# dac_wifi.net
KiCad netlist of a schematic drawn in EAGLE
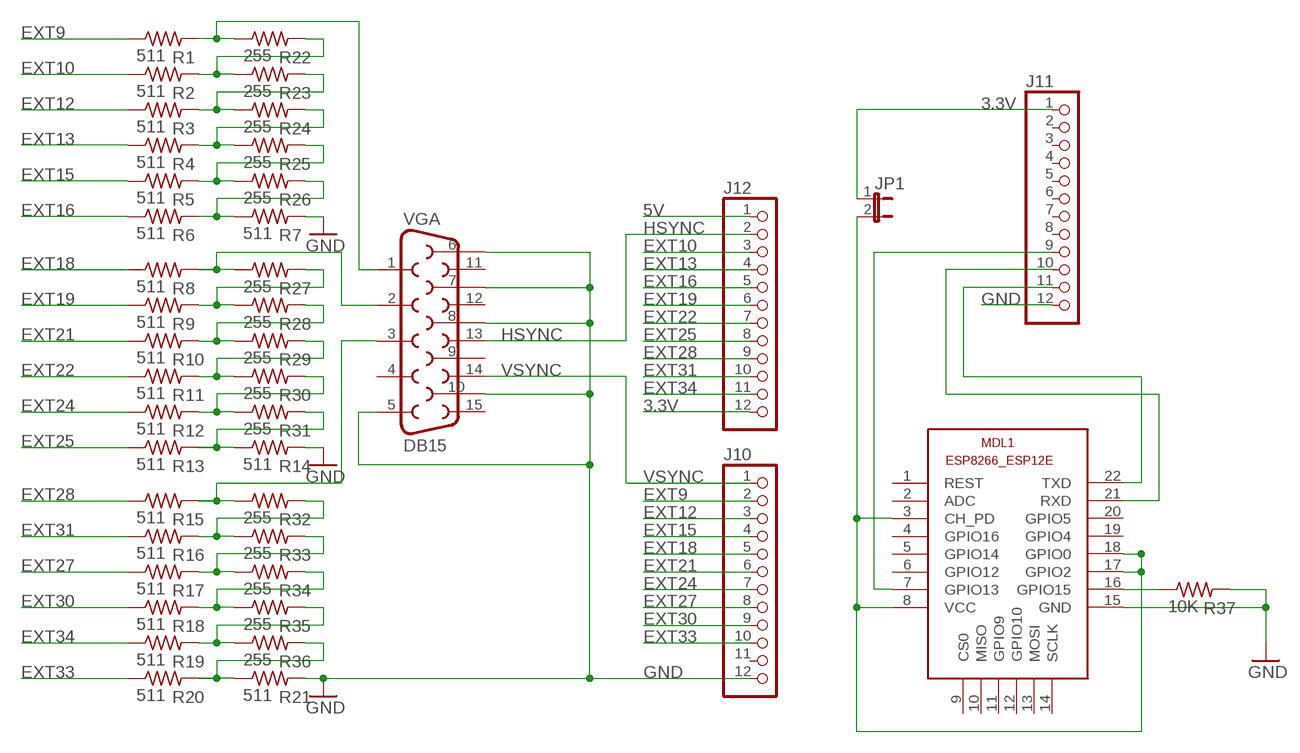
[diagram p0: schematic, sheet 1]

(export (version "E")
  (design (tool "Eeschema 10.0.6"))
  (components
    (comp (ref "J10")
      (value "PINHD-1X12")
      (footprint "eagle-import:1X12")
      (libsource (lib "eagle-import") (part "PINHD-1X12"))
    )
    (comp (ref "J11")
      (value "PINHD-1X12")
      (footprint "eagle-import:1X12")
      (libsource (lib "eagle-import") (part "PINHD-1X12"))
    )
    (comp (ref "J12")
      (value "PINHD-1X12")
      (footprint "eagle-import:1X12")
      (libsource (lib "eagle-import") (part "PINHD-1X12"))
    )
    (comp (ref "JP1")
      (value "JP1E")
      (footprint "eagle-import:JP1")
      (libsource (lib "eagle-import") (part "JP1E"))
    )
    (comp (ref "MDL1")
      (value "ESP8266-12EESP8266-ESP12E")
      (footprint "eagle-import:ESP8266-ESP12E")
      (libsource (lib "eagle-import") (part "ESP8266-12EESP8266-ESP12E"))
    )
    (comp (ref "R1")
      (value "511")
      (footprint "eagle-import:R0805")
      (libsource (lib "eagle-import") (part "R-US_R0805"))
    )
    (comp (ref "R2")
      (value "511")
      (footprint "eagle-import:R0805")
      (libsource (lib "eagle-import") (part "R-US_R0805"))
    )
    (comp (ref "R3")
      (value "511")
      (footprint "eagle-import:R0805")
      (libsource (lib "eagle-import") (part "R-US_R0805"))
    )
    (comp (ref "R4")
      (value "511")
      (footprint "eagle-import:R0805")
      (libsource (lib "eagle-import") (part "R-US_R0805"))
    )
    (comp (ref "R5")
      (value "511")
      (footprint "eagle-import:R0805")
      (libsource (lib "eagle-import") (part "R-US_R0805"))
    )
    (comp (ref "R6")
      (value "511")
      (footprint "eagle-import:R0805")
      (libsource (lib "eagle-import") (part "R-US_R0805"))
    )
    (comp (ref "R7")
      (value "511")
      (footprint "eagle-import:R0805")
      (libsource (lib "eagle-import") (part "R-US_R0805"))
    )
    (comp (ref "R8")
      (value "511")
      (footprint "eagle-import:R0805")
      (libsource (lib "eagle-import") (part "R-US_R0805"))
    )
    (comp (ref "R9")
      (value "511")
      (footprint "eagle-import:R0805")
      (libsource (lib "eagle-import") (part "R-US_R0805"))
    )
    (comp (ref "R10")
      (value "511")
      (footprint "eagle-import:R0805")
      (libsource (lib "eagle-import") (part "R-US_R0805"))
    )
    (comp (ref "R11")
      (value "511")
      (footprint "eagle-import:R0805")
      (libsource (lib "eagle-import") (part "R-US_R0805"))
    )
    (comp (ref "R12")
      (value "511")
      (footprint "eagle-import:R0805")
      (libsource (lib "eagle-import") (part "R-US_R0805"))
    )
    (comp (ref "R13")
      (value "511")
      (footprint "eagle-import:R0805")
      (libsource (lib "eagle-import") (part "R-US_R0805"))
    )
    (comp (ref "R14")
      (value "511")
      (footprint "eagle-import:R0805")
      (libsource (lib "eagle-import") (part "R-US_R0805"))
    )
    (comp (ref "R15")
      (value "511")
      (footprint "eagle-import:R0805")
      (libsource (lib "eagle-import") (part "R-US_R0805"))
    )
    (comp (ref "R16")
      (value "511")
      (footprint "eagle-import:R0805")
      (libsource (lib "eagle-import") (part "R-US_R0805"))
    )
    (comp (ref "R17")
      (value "511")
      (footprint "eagle-import:R0805")
      (libsource (lib "eagle-import") (part "R-US_R0805"))
    )
    (comp (ref "R18")
      (value "511")
      (footprint "eagle-import:R0805")
      (libsource (lib "eagle-import") (part "R-US_R0805"))
    )
    (comp (ref "R19")
      (value "511")
      (footprint "eagle-import:R0805")
      (libsource (lib "eagle-import") (part "R-US_R0805"))
    )
    (comp (ref "R20")
      (value "511")
      (footprint "eagle-import:R0805")
      (libsource (lib "eagle-import") (part "R-US_R0805"))
    )
    (comp (ref "R21")
      (value "511")
      (footprint "eagle-import:R0805")
      (libsource (lib "eagle-import") (part "R-US_R0805"))
    )
    (comp (ref "R22")
      (value "255")
      (footprint "eagle-import:R0805")
      (libsource (lib "eagle-import") (part "R-US_R0805"))
    )
    (comp (ref "R23")
      (value "255")
      (footprint "eagle-import:R0805")
      (libsource (lib "eagle-import") (part "R-US_R0805"))
    )
    (comp (ref "R24")
      (value "255")
      (footprint "eagle-import:R0805")
      (libsource (lib "eagle-import") (part "R-US_R0805"))
    )
    (comp (ref "R25")
      (value "255")
      (footprint "eagle-import:R0805")
      (libsource (lib "eagle-import") (part "R-US_R0805"))
    )
    (comp (ref "R26")
      (value "255")
      (footprint "eagle-import:R0805")
      (libsource (lib "eagle-import") (part "R-US_R0805"))
    )
    (comp (ref "R27")
      (value "255")
      (footprint "eagle-import:R0805")
      (libsource (lib "eagle-import") (part "R-US_R0805"))
    )
    (comp (ref "R28")
      (value "255")
      (footprint "eagle-import:R0805")
      (libsource (lib "eagle-import") (part "R-US_R0805"))
    )
    (comp (ref "R29")
      (value "255")
      (footprint "eagle-import:R0805")
      (libsource (lib "eagle-import") (part "R-US_R0805"))
    )
    (comp (ref "R30")
      (value "255")
      (footprint "eagle-import:R0805")
      (libsource (lib "eagle-import") (part "R-US_R0805"))
    )
    (comp (ref "R31")
      (value "255")
      (footprint "eagle-import:R0805")
      (libsource (lib "eagle-import") (part "R-US_R0805"))
    )
    (comp (ref "R32")
      (value "255")
      (footprint "eagle-import:R0805")
      (libsource (lib "eagle-import") (part "R-US_R0805"))
    )
    (comp (ref "R33")
      (value "255")
      (footprint "eagle-import:R0805")
      (libsource (lib "eagle-import") (part "R-US_R0805"))
    )
    (comp (ref "R34")
      (value "255")
      (footprint "eagle-import:R0805")
      (libsource (lib "eagle-import") (part "R-US_R0805"))
    )
    (comp (ref "R35")
      (value "255")
      (footprint "eagle-import:R0805")
      (libsource (lib "eagle-import") (part "R-US_R0805"))
    )
    (comp (ref "R36")
      (value "255")
      (footprint "eagle-import:R0805")
      (libsource (lib "eagle-import") (part "R-US_R0805"))
    )
    (comp (ref "R37")
      (value "10K")
      (footprint "eagle-import:R0805")
      (libsource (lib "eagle-import") (part "R-US_R0805"))
    )
    (comp (ref "VGA")
      (value "DB15")
      (footprint "eagle-import:DB15")
      (libsource (lib "eagle-import") (part "DB15"))
    )
  )
  (nets
    (net (code "1") (name "/3.3V") (class "Default")
      (node (ref "J11") (pin "1") (pinfunction "1_1") (pintype "passive"))
      (node (ref "J12") (pin "12") (pinfunction "12_12") (pintype "passive"))
      (node (ref "JP1") (pin "1") (pinfunction "1_1") (pintype "passive"))
    )
    (net (code "2") (name "/5V") (class "Default")
      (node (ref "J12") (pin "1") (pinfunction "1_1") (pintype "passive"))
    )
    (net (code "3") (name "/EXT9") (class "Default")
      (node (ref "J10") (pin "2") (pinfunction "2_2") (pintype "passive"))
      (node (ref "R1") (pin "1") (pinfunction "1_1") (pintype "passive"))
    )
    (net (code "4") (name "/EXT10") (class "Default")
      (node (ref "J12") (pin "3") (pinfunction "3_3") (pintype "passive"))
      (node (ref "R2") (pin "1") (pinfunction "1_1") (pintype "passive"))
    )
    (net (code "5") (name "/EXT12") (class "Default")
      (node (ref "J10") (pin "3") (pinfunction "3_3") (pintype "passive"))
      (node (ref "R3") (pin "1") (pinfunction "1_1") (pintype "passive"))
    )
    (net (code "6") (name "/EXT13") (class "Default")
      (node (ref "J12") (pin "4") (pinfunction "4_4") (pintype "passive"))
      (node (ref "R4") (pin "1") (pinfunction "1_1") (pintype "passive"))
    )
    (net (code "7") (name "/EXT15") (class "Default")
      (node (ref "J10") (pin "4") (pinfunction "4_4") (pintype "passive"))
      (node (ref "R5") (pin "1") (pinfunction "1_1") (pintype "passive"))
    )
    (net (code "8") (name "/EXT16") (class "Default")
      (node (ref "J12") (pin "5") (pinfunction "5_5") (pintype "passive"))
      (node (ref "R6") (pin "1") (pinfunction "1_1") (pintype "passive"))
    )
    (net (code "9") (name "/EXT18") (class "Default")
      (node (ref "J10") (pin "5") (pinfunction "5_5") (pintype "passive"))
      (node (ref "R8") (pin "1") (pinfunction "1_1") (pintype "passive"))
    )
    (net (code "10") (name "/EXT19") (class "Default")
      (node (ref "J12") (pin "6") (pinfunction "6_6") (pintype "passive"))
      (node (ref "R9") (pin "1") (pinfunction "1_1") (pintype "passive"))
    )
    (net (code "11") (name "/EXT21") (class "Default")
      (node (ref "J10") (pin "6") (pinfunction "6_6") (pintype "passive"))
      (node (ref "R10") (pin "1") (pinfunction "1_1") (pintype "passive"))
    )
    (net (code "12") (name "/EXT22") (class "Default")
      (node (ref "J12") (pin "7") (pinfunction "7_7") (pintype "passive"))
      (node (ref "R11") (pin "1") (pinfunction "1_1") (pintype "passive"))
    )
    (net (code "13") (name "/EXT24") (class "Default")
      (node (ref "J10") (pin "7") (pinfunction "7_7") (pintype "passive"))
      (node (ref "R12") (pin "1") (pinfunction "1_1") (pintype "passive"))
    )
    (net (code "14") (name "/EXT25") (class "Default")
      (node (ref "J12") (pin "8") (pinfunction "8_8") (pintype "passive"))
      (node (ref "R13") (pin "1") (pinfunction "1_1") (pintype "passive"))
    )
    (net (code "15") (name "/EXT27") (class "Default")
      (node (ref "J10") (pin "8") (pinfunction "8_8") (pintype "passive"))
      (node (ref "R17") (pin "1") (pinfunction "1_1") (pintype "passive"))
    )
    (net (code "16") (name "/EXT28") (class "Default")
      (node (ref "J12") (pin "9") (pinfunction "9_9") (pintype "passive"))
      (node (ref "R15") (pin "1") (pinfunction "1_1") (pintype "passive"))
    )
    (net (code "17") (name "/EXT30") (class "Default")
      (node (ref "J10") (pin "9") (pinfunction "9_9") (pintype "passive"))
      (node (ref "R18") (pin "1") (pinfunction "1_1") (pintype "passive"))
    )
    (net (code "18") (name "/EXT31") (class "Default")
      (node (ref "J12") (pin "10") (pinfunction "10_10") (pintype "passive"))
      (node (ref "R16") (pin "1") (pinfunction "1_1") (pintype "passive"))
    )
    (net (code "19") (name "/EXT33") (class "Default")
      (node (ref "J10") (pin "10") (pinfunction "10_10") (pintype "passive"))
      (node (ref "R20") (pin "1") (pinfunction "1_1") (pintype "passive"))
    )
    (net (code "20") (name "/EXT34") (class "Default")
      (node (ref "J12") (pin "11") (pinfunction "11_11") (pintype "passive"))
      (node (ref "R19") (pin "1") (pinfunction "1_1") (pintype "passive"))
    )
    (net (code "21") (name "/HSYNC") (class "Default")
      (node (ref "J12") (pin "2") (pinfunction "2_2") (pintype "passive"))
      (node (ref "VGA") (pin "13") (pinfunction "13_13") (pintype "passive"))
    )
    (net (code "22") (name "/VSYNC") (class "Default")
      (node (ref "J10") (pin "1") (pinfunction "1_1") (pintype "passive"))
      (node (ref "VGA") (pin "14") (pinfunction "14_14") (pintype "passive"))
    )
    (net (code "23") (name "GND") (class "Default")
      (node (ref "J10") (pin "12") (pinfunction "12_12") (pintype "passive"))
      (node (ref "J11") (pin "12") (pinfunction "12_12") (pintype "passive"))
      (node (ref "MDL1") (pin "15") (pinfunction "GND_15") (pintype "bidirectional"))
      (node (ref "R14") (pin "2") (pinfunction "2_2") (pintype "passive"))
      (node (ref "R21") (pin "2") (pinfunction "2_2") (pintype "passive"))
      (node (ref "R37") (pin "2") (pinfunction "2_2") (pintype "passive"))
      (node (ref "R7") (pin "2") (pinfunction "2_2") (pintype "passive"))
      (node (ref "VGA") (pin "10") (pinfunction "10_10") (pintype "passive"))
      (node (ref "VGA") (pin "5") (pinfunction "5_5") (pintype "passive"))
      (node (ref "VGA") (pin "6") (pinfunction "6_6") (pintype "passive"))
      (node (ref "VGA") (pin "7") (pinfunction "7_7") (pintype "passive"))
      (node (ref "VGA") (pin "8") (pinfunction "8_8") (pintype "passive"))
    )
    (net (code "24") (name "Net-(MDL1-CH_PD)") (class "Default")
      (node (ref "JP1") (pin "2") (pinfunction "2_2") (pintype "passive"))
      (node (ref "MDL1") (pin "17") (pinfunction "GPIO2_17") (pintype "bidirectional"))
      (node (ref "MDL1") (pin "18") (pinfunction "GPIO0_18") (pintype "bidirectional"))
      (node (ref "MDL1") (pin "3") (pinfunction "CH_PD_3") (pintype "bidirectional"))
      (node (ref "MDL1") (pin "8") (pinfunction "VCC_8") (pintype "bidirectional"))
    )
    (net (code "25") (name "Net-(MDL1-GPIO13)") (class "Default")
      (node (ref "J11") (pin "9") (pinfunction "9_9") (pintype "passive"))
      (node (ref "MDL1") (pin "7") (pinfunction "GPIO13_7") (pintype "bidirectional"))
    )
    (net (code "26") (name "Net-(MDL1-GPIO15)") (class "Default")
      (node (ref "MDL1") (pin "16") (pinfunction "GPIO15_16") (pintype "bidirectional"))
      (node (ref "R37") (pin "1") (pinfunction "1_1") (pintype "passive"))
    )
    (net (code "27") (name "Net-(MDL1-RXD)") (class "Default")
      (node (ref "J11") (pin "10") (pinfunction "10_10") (pintype "passive"))
      (node (ref "MDL1") (pin "21") (pinfunction "RXD_21") (pintype "bidirectional"))
    )
    (net (code "28") (name "Net-(MDL1-TXD)") (class "Default")
      (node (ref "J11") (pin "11") (pinfunction "11_11") (pintype "passive"))
      (node (ref "MDL1") (pin "22") (pinfunction "TXD_22") (pintype "bidirectional"))
    )
    (net (code "29") (name "Net-(R1-Pad2)") (class "Default")
      (node (ref "R1") (pin "2") (pinfunction "2_2") (pintype "passive"))
      (node (ref "R22") (pin "1") (pinfunction "1_1") (pintype "passive"))
      (node (ref "VGA") (pin "1") (pinfunction "1_1") (pintype "passive"))
    )
    (net (code "30") (name "Net-(R2-Pad2)") (class "Default")
      (node (ref "R2") (pin "2") (pinfunction "2_2") (pintype "passive"))
      (node (ref "R22") (pin "2") (pinfunction "2_2") (pintype "passive"))
      (node (ref "R23") (pin "1") (pinfunction "1_1") (pintype "passive"))
    )
    (net (code "31") (name "Net-(R10-Pad2)") (class "Default")
      (node (ref "R10") (pin "2") (pinfunction "2_2") (pintype "passive"))
      (node (ref "R28") (pin "2") (pinfunction "2_2") (pintype "passive"))
      (node (ref "R29") (pin "1") (pinfunction "1_1") (pintype "passive"))
    )
    (net (code "32") (name "Net-(R11-Pad2)") (class "Default")
      (node (ref "R11") (pin "2") (pinfunction "2_2") (pintype "passive"))
      (node (ref "R29") (pin "2") (pinfunction "2_2") (pintype "passive"))
      (node (ref "R30") (pin "1") (pinfunction "1_1") (pintype "passive"))
    )
    (net (code "33") (name "Net-(R12-Pad2)") (class "Default")
      (node (ref "R12") (pin "2") (pinfunction "2_2") (pintype "passive"))
      (node (ref "R30") (pin "2") (pinfunction "2_2") (pintype "passive"))
      (node (ref "R31") (pin "1") (pinfunction "1_1") (pintype "passive"))
    )
    (net (code "34") (name "Net-(R13-Pad2)") (class "Default")
      (node (ref "R13") (pin "2") (pinfunction "2_2") (pintype "passive"))
      (node (ref "R14") (pin "1") (pinfunction "1_1") (pintype "passive"))
      (node (ref "R31") (pin "2") (pinfunction "2_2") (pintype "passive"))
    )
    (net (code "35") (name "Net-(R15-Pad2)") (class "Default")
      (node (ref "R15") (pin "2") (pinfunction "2_2") (pintype "passive"))
      (node (ref "R32") (pin "1") (pinfunction "1_1") (pintype "passive"))
      (node (ref "VGA") (pin "3") (pinfunction "3_3") (pintype "passive"))
    )
    (net (code "36") (name "Net-(R16-Pad2)") (class "Default")
      (node (ref "R16") (pin "2") (pinfunction "2_2") (pintype "passive"))
      (node (ref "R32") (pin "2") (pinfunction "2_2") (pintype "passive"))
      (node (ref "R33") (pin "1") (pinfunction "1_1") (pintype "passive"))
    )
    (net (code "37") (name "Net-(R17-Pad2)") (class "Default")
      (node (ref "R17") (pin "2") (pinfunction "2_2") (pintype "passive"))
      (node (ref "R33") (pin "2") (pinfunction "2_2") (pintype "passive"))
      (node (ref "R34") (pin "1") (pinfunction "1_1") (pintype "passive"))
    )
    (net (code "38") (name "Net-(R18-Pad2)") (class "Default")
      (node (ref "R18") (pin "2") (pinfunction "2_2") (pintype "passive"))
      (node (ref "R34") (pin "2") (pinfunction "2_2") (pintype "passive"))
      (node (ref "R35") (pin "1") (pinfunction "1_1") (pintype "passive"))
    )
    (net (code "39") (name "Net-(R19-Pad2)") (class "Default")
      (node (ref "R19") (pin "2") (pinfunction "2_2") (pintype "passive"))
      (node (ref "R35") (pin "2") (pinfunction "2_2") (pintype "passive"))
      (node (ref "R36") (pin "1") (pinfunction "1_1") (pintype "passive"))
    )
    (net (code "40") (name "Net-(R20-Pad2)") (class "Default")
      (node (ref "R20") (pin "2") (pinfunction "2_2") (pintype "passive"))
      (node (ref "R21") (pin "1") (pinfunction "1_1") (pintype "passive"))
      (node (ref "R36") (pin "2") (pinfunction "2_2") (pintype "passive"))
    )
    (net (code "41") (name "Net-(R23-Pad2)") (class "Default")
      (node (ref "R23") (pin "2") (pinfunction "2_2") (pintype "passive"))
      (node (ref "R24") (pin "1") (pinfunction "1_1") (pintype "passive"))
      (node (ref "R3") (pin "2") (pinfunction "2_2") (pintype "passive"))
    )
    (net (code "42") (name "Net-(R24-Pad2)") (class "Default")
      (node (ref "R24") (pin "2") (pinfunction "2_2") (pintype "passive"))
      (node (ref "R25") (pin "1") (pinfunction "1_1") (pintype "passive"))
      (node (ref "R4") (pin "2") (pinfunction "2_2") (pintype "passive"))
    )
    (net (code "43") (name "Net-(R25-Pad2)") (class "Default")
      (node (ref "R25") (pin "2") (pinfunction "2_2") (pintype "passive"))
      (node (ref "R26") (pin "1") (pinfunction "1_1") (pintype "passive"))
      (node (ref "R5") (pin "2") (pinfunction "2_2") (pintype "passive"))
    )
    (net (code "44") (name "Net-(R26-Pad2)") (class "Default")
      (node (ref "R26") (pin "2") (pinfunction "2_2") (pintype "passive"))
      (node (ref "R6") (pin "2") (pinfunction "2_2") (pintype "passive"))
      (node (ref "R7") (pin "1") (pinfunction "1_1") (pintype "passive"))
    )
    (net (code "45") (name "Net-(R27-Pad1)") (class "Default")
      (node (ref "R27") (pin "1") (pinfunction "1_1") (pintype "passive"))
      (node (ref "R8") (pin "2") (pinfunction "2_2") (pintype "passive"))
      (node (ref "VGA") (pin "2") (pinfunction "2_2") (pintype "passive"))
    )
    (net (code "46") (name "Net-(R27-Pad2)") (class "Default")
      (node (ref "R27") (pin "2") (pinfunction "2_2") (pintype "passive"))
      (node (ref "R28") (pin "1") (pinfunction "1_1") (pintype "passive"))
      (node (ref "R9") (pin "2") (pinfunction "2_2") (pintype "passive"))
    )
    (net (code "47") (name "unconnected-(J10-Pad11)") (class "Default")
      (node (ref "J10") (pin "11") (pinfunction "11_11") (pintype "passive"))
    )
    (net (code "48") (name "unconnected-(J11-Pad2)") (class "Default")
      (node (ref "J11") (pin "2") (pinfunction "2_2") (pintype "passive"))
    )
    (net (code "49") (name "unconnected-(J11-Pad3)") (class "Default")
      (node (ref "J11") (pin "3") (pinfunction "3_3") (pintype "passive"))
    )
    (net (code "50") (name "unconnected-(J11-Pad4)") (class "Default")
      (node (ref "J11") (pin "4") (pinfunction "4_4") (pintype "passive"))
    )
    (net (code "51") (name "unconnected-(J11-Pad5)") (class "Default")
      (node (ref "J11") (pin "5") (pinfunction "5_5") (pintype "passive"))
    )
    (net (code "52") (name "unconnected-(J11-Pad6)") (class "Default")
      (node (ref "J11") (pin "6") (pinfunction "6_6") (pintype "passive"))
    )
    (net (code "53") (name "unconnected-(J11-Pad7)") (class "Default")
      (node (ref "J11") (pin "7") (pinfunction "7_7") (pintype "passive"))
    )
    (net (code "54") (name "unconnected-(J11-Pad8)") (class "Default")
      (node (ref "J11") (pin "8") (pinfunction "8_8") (pintype "passive"))
    )
    (net (code "55") (name "unconnected-(MDL1-ADC-Pad2)") (class "Default")
      (node (ref "MDL1") (pin "2") (pinfunction "ADC_2") (pintype "bidirectional"))
    )
    (net (code "56") (name "unconnected-(MDL1-CS0-Pad9)") (class "Default")
      (node (ref "MDL1") (pin "9") (pinfunction "CS0_9") (pintype "bidirectional"))
    )
    (net (code "57") (name "unconnected-(MDL1-GPIO4-Pad19)") (class "Default")
      (node (ref "MDL1") (pin "19") (pinfunction "GPIO4_19") (pintype "bidirectional"))
    )
    (net (code "58") (name "unconnected-(MDL1-GPIO5-Pad20)") (class "Default")
      (node (ref "MDL1") (pin "20") (pinfunction "GPIO5_20") (pintype "bidirectional"))
    )
    (net (code "59") (name "unconnected-(MDL1-GPIO9-Pad11)") (class "Default")
      (node (ref "MDL1") (pin "11") (pinfunction "GPIO9_11") (pintype "bidirectional"))
    )
    (net (code "60") (name "unconnected-(MDL1-GPIO10-Pad12)") (class "Default")
      (node (ref "MDL1") (pin "12") (pinfunction "GPIO10_12") (pintype "bidirectional"))
    )
    (net (code "61") (name "unconnected-(MDL1-GPIO12-Pad6)") (class "Default")
      (node (ref "MDL1") (pin "6") (pinfunction "GPIO12_6") (pintype "bidirectional"))
    )
    (net (code "62") (name "unconnected-(MDL1-GPIO14-Pad5)") (class "Default")
      (node (ref "MDL1") (pin "5") (pinfunction "GPIO14_5") (pintype "bidirectional"))
    )
    (net (code "63") (name "unconnected-(MDL1-GPIO16-Pad4)") (class "Default")
      (node (ref "MDL1") (pin "4") (pinfunction "GPIO16_4") (pintype "bidirectional"))
    )
    (net (code "64") (name "unconnected-(MDL1-MISO-Pad10)") (class "Default")
      (node (ref "MDL1") (pin "10") (pinfunction "MISO_10") (pintype "bidirectional"))
    )
    (net (code "65") (name "unconnected-(MDL1-MOSI-Pad13)") (class "Default")
      (node (ref "MDL1") (pin "13") (pinfunction "MOSI_13") (pintype "bidirectional"))
    )
    (net (code "66") (name "unconnected-(MDL1-REST-Pad1)") (class "Default")
      (node (ref "MDL1") (pin "1") (pinfunction "REST_1") (pintype "bidirectional"))
    )
    (net (code "67") (name "unconnected-(MDL1-SCLK-Pad14)") (class "Default")
      (node (ref "MDL1") (pin "14") (pinfunction "SCLK_14") (pintype "bidirectional"))
    )
    (net (code "68") (name "unconnected-(VGA-Pad4)") (class "Default")
      (node (ref "VGA") (pin "4") (pinfunction "4_4") (pintype "passive"))
    )
    (net (code "69") (name "unconnected-(VGA-Pad9)") (class "Default")
      (node (ref "VGA") (pin "9") (pinfunction "9_9") (pintype "passive"))
    )
    (net (code "70") (name "unconnected-(VGA-Pad11)") (class "Default")
      (node (ref "VGA") (pin "11") (pinfunction "11_11") (pintype "passive"))
    )
    (net (code "71") (name "unconnected-(VGA-Pad12)") (class "Default")
      (node (ref "VGA") (pin "12") (pinfunction "12_12") (pintype "passive"))
    )
    (net (code "72") (name "unconnected-(VGA-Pad15)") (class "Default")
      (node (ref "VGA") (pin "15") (pinfunction "15_15") (pintype "passive"))
    )
  )
)
